# layout.net
KiCad netlist of a schematic drawn in EAGLE
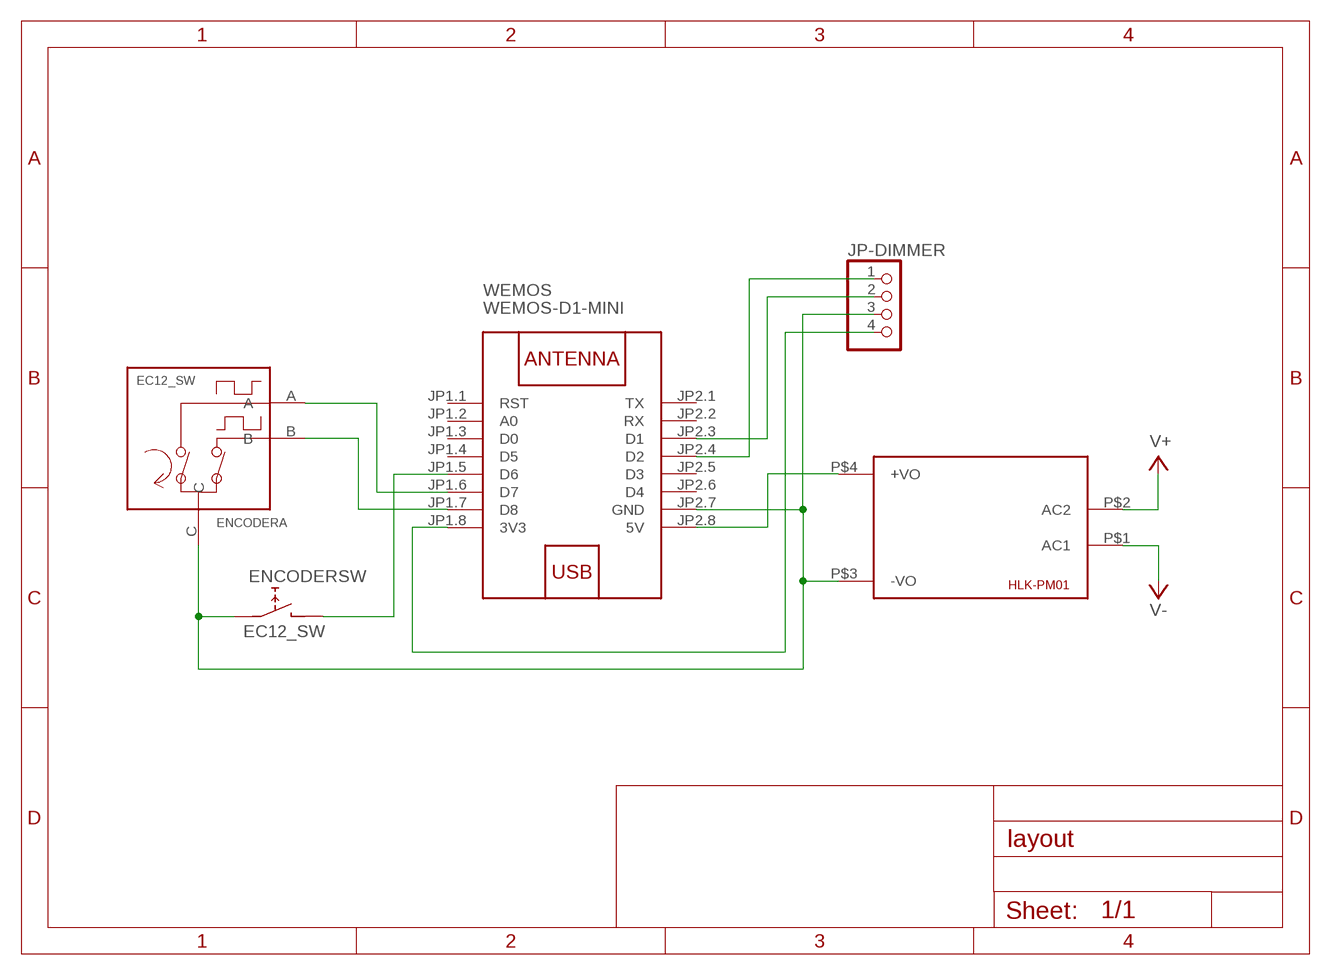
[diagram p0: schematic, sheet 1]

(export (version "E")
  (design (tool "Eeschema 10.0.6"))
  (components
    (comp (ref "ENCODER")
      (value "EC12_SW")
      (footprint "eagle-import:EC12S")
      (libsource (lib "eagle-import") (part "EC12_SW"))
    )
    (comp (ref "HLK-PM01")
      (value "HLK-PM013W")
      (footprint "eagle-import:HLK-PM01")
      (libsource (lib "eagle-import") (part "HLK-PM013W"))
    )
    (comp (ref "JP-DIMMER")
      (value "PINHD-1X4")
      (footprint "eagle-import:1X04")
      (libsource (lib "eagle-import") (part "PINHD-1X4"))
    )
    (comp (ref "WEMOS")
      (value "WEMOS-D1-MINI")
      (footprint "eagle-import:WEMOS-D1-MINI")
      (libsource (lib "eagle-import") (part "WEMOS-D1-MINI"))
    )
  )
  (nets
    (net (code "1") (name "Net-(HLK-PM01-+VO)") (class "Default")
      (node (ref "HLK-PM01") (pin "P$4") (pinfunction "+VO_P$4") (pintype "bidirectional"))
      (node (ref "WEMOS") (pin "JP2.8") (pinfunction "5V_JP2.8") (pintype "power_in"))
    )
    (net (code "2") (name "Net-(HLK-PM01--VO)") (class "Default")
      (node (ref "ENCODER") (pin "C") (pinfunction "C_C") (pintype "bidirectional"))
      (node (ref "ENCODER") (pin "D") (pinfunction "D_D") (pintype "passive"))
      (node (ref "HLK-PM01") (pin "P$3") (pinfunction "-VO_P$3") (pintype "bidirectional"))
      (node (ref "JP-DIMMER") (pin "3") (pinfunction "3_3") (pintype "passive"))
      (node (ref "WEMOS") (pin "JP2.7") (pinfunction "GND_JP2.7") (pintype "power_in"))
    )
    (net (code "3") (name "Net-(WEMOS-3V3)") (class "Default")
      (node (ref "JP-DIMMER") (pin "4") (pinfunction "4_4") (pintype "passive"))
      (node (ref "WEMOS") (pin "JP1.8") (pinfunction "3V3_JP1.8") (pintype "power_in"))
    )
    (net (code "4") (name "Net-(WEMOS-D1)") (class "Default")
      (node (ref "JP-DIMMER") (pin "2") (pinfunction "2_2") (pintype "passive"))
      (node (ref "WEMOS") (pin "JP2.3") (pinfunction "D1_JP2.3") (pintype "bidirectional"))
    )
    (net (code "5") (name "Net-(WEMOS-D2)") (class "Default")
      (node (ref "JP-DIMMER") (pin "1") (pinfunction "1_1") (pintype "passive"))
      (node (ref "WEMOS") (pin "JP2.4") (pinfunction "D2_JP2.4") (pintype "bidirectional"))
    )
    (net (code "6") (name "Net-(WEMOS-D6)") (class "Default")
      (node (ref "ENCODER") (pin "E") (pinfunction "E_E") (pintype "passive"))
      (node (ref "WEMOS") (pin "JP1.5") (pinfunction "D6_JP1.5") (pintype "bidirectional"))
    )
    (net (code "7") (name "Net-(WEMOS-D7)") (class "Default")
      (node (ref "ENCODER") (pin "A") (pinfunction "A_A") (pintype "bidirectional"))
      (node (ref "WEMOS") (pin "JP1.6") (pinfunction "D7_JP1.6") (pintype "bidirectional"))
    )
    (net (code "8") (name "Net-(WEMOS-D8)") (class "Default")
      (node (ref "ENCODER") (pin "B") (pinfunction "B_B") (pintype "bidirectional"))
      (node (ref "WEMOS") (pin "JP1.7") (pinfunction "D8_JP1.7") (pintype "bidirectional"))
    )
    (net (code "9") (name "V+") (class "Default")
      (node (ref "HLK-PM01") (pin "P$2") (pinfunction "AC2_P$2") (pintype "bidirectional"))
    )
    (net (code "10") (name "V-") (class "Default")
      (node (ref "HLK-PM01") (pin "P$1") (pinfunction "AC1_P$1") (pintype "bidirectional"))
    )
    (net (code "11") (name "unconnected-(WEMOS-A0-PadJP1.2)") (class "Default")
      (node (ref "WEMOS") (pin "JP1.2") (pinfunction "A0_JP1.2") (pintype "bidirectional"))
    )
    (net (code "12") (name "unconnected-(WEMOS-D0-PadJP1.3)") (class "Default")
      (node (ref "WEMOS") (pin "JP1.3") (pinfunction "D0_JP1.3") (pintype "bidirectional"))
    )
    (net (code "13") (name "unconnected-(WEMOS-D3-PadJP2.5)") (class "Default")
      (node (ref "WEMOS") (pin "JP2.5") (pinfunction "D3_JP2.5") (pintype "bidirectional"))
    )
    (net (code "14") (name "unconnected-(WEMOS-D4-PadJP2.6)") (class "Default")
      (node (ref "WEMOS") (pin "JP2.6") (pinfunction "D4_JP2.6") (pintype "bidirectional"))
    )
    (net (code "15") (name "unconnected-(WEMOS-D5-PadJP1.4)") (class "Default")
      (node (ref "WEMOS") (pin "JP1.4") (pinfunction "D5_JP1.4") (pintype "bidirectional"))
    )
    (net (code "16") (name "unconnected-(WEMOS-RST-PadJP1.1)") (class "Default")
      (node (ref "WEMOS") (pin "JP1.1") (pinfunction "RST_JP1.1") (pintype "bidirectional"))
    )
    (net (code "17") (name "unconnected-(WEMOS-RX-PadJP2.2)") (class "Default")
      (node (ref "WEMOS") (pin "JP2.2") (pinfunction "RX_JP2.2") (pintype "bidirectional"))
    )
    (net (code "18") (name "unconnected-(WEMOS-TX-PadJP2.1)") (class "Default")
      (node (ref "WEMOS") (pin "JP2.1") (pinfunction "TX_JP2.1") (pintype "bidirectional"))
    )
  )
)
